# Connectors.net
KiCad netlist of a schematic drawn in Altium Designer
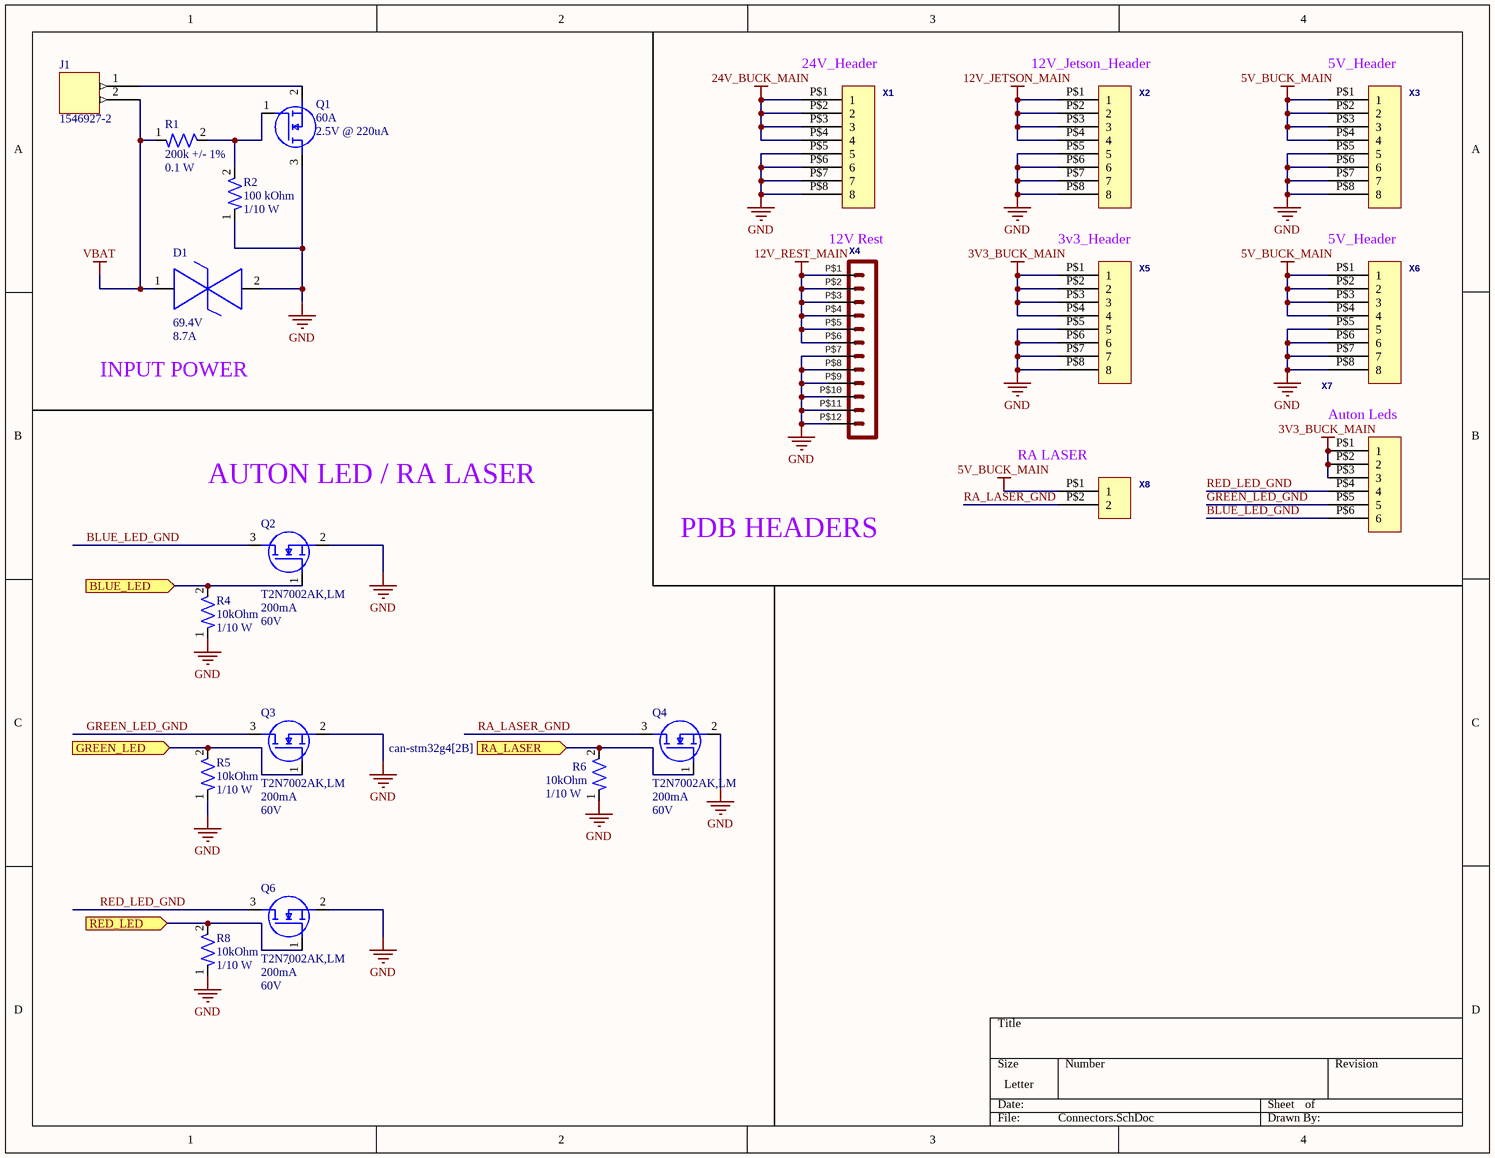
[diagram p0: Connectors.SchDoc]

(export (version "E")
  (design (tool "Eeschema 10.0.6"))
  (components
    (comp (ref "D1")
      (value "SMBJE43CAH")
      (footprint "DO-214AA (SMBJ)")
      (description "69.4V Clamp 8.7A Ipp Tvs Diode Surface Mount DO-214AA (SMBJ)")
      (fields (field (name "VCLAMP") "69.4V") (field (name "PEAK PULSER CURRENT") "8.7A"))
      (libsource (lib "MasterLib") (part "DIO-69.4V-0001"))
    )
    (comp (ref "J1")
      (value "1546927-2")
      (footprint "CONN-1546927-2")
      (libsource (lib "MasterLib") (part "CON-2POS-0003"))
    )
    (comp (ref "Q1")
      (value "TPH7R006PL,L1Q")
      (footprint "NMOS-8PowerVDFN")
      (description "N-Channel 60 V 60A (Tc) 81W (Tc) Surface Mount 8-SOP Advance (5x5)")
      (fields (field (name "DRAIN CURRENT") "60A") (field (name "VGS") "2.5V @ 220uA"))
      (libsource (lib "MasterLib") (part "NMOS-60A-0001"))
    )
    (comp (ref "Q2")
      (value "T2N7002AK,LM")
      (footprint "NMOS-SOT23-3")
      (description "MOSFET N-CH 60V 200MA SOT23")
      (fields
        (field (name "MANUFACTURER") "Toshiba")
        (field (name "ID-CONTINUOUS") "200mA")
        (field (name "VDS-MAX") "60V")
      )
      (libsource (lib "MasterLib") (part "NMOS-200MA-0001"))
    )
    (comp (ref "Q3")
      (value "T2N7002AK,LM")
      (footprint "NMOS-SOT23-3")
      (description "MOSFET N-CH 60V 200MA SOT23")
      (fields
        (field (name "MANUFACTURER") "Toshiba")
        (field (name "ID-CONTINUOUS") "200mA")
        (field (name "VDS-MAX") "60V")
      )
      (libsource (lib "MasterLib") (part "NMOS-200MA-0001"))
    )
    (comp (ref "Q4")
      (value "T2N7002AK,LM")
      (footprint "NMOS-SOT23-3")
      (description "MOSFET N-CH 60V 200MA SOT23")
      (fields
        (field (name "MANUFACTURER") "Toshiba")
        (field (name "ID-CONTINUOUS") "200mA")
        (field (name "VDS-MAX") "60V")
      )
      (libsource (lib "MasterLib") (part "NMOS-200MA-0001"))
    )
    (comp (ref "Q6")
      (value "T2N7002AK,LM")
      (footprint "NMOS-SOT23-3")
      (description "MOSFET N-CH 60V 200MA SOT23")
      (fields
        (field (name "MANUFACTURER") "Toshiba")
        (field (name "ID-CONTINUOUS") "200mA")
        (field (name "VDS-MAX") "60V")
      )
      (libsource (lib "MasterLib") (part "NMOS-200MA-0001"))
    )
    (comp (ref "R1")
      (value "ERJ-3EKF2003V")
      (footprint "RES-0603")
      (description "200 kOhms ±1% 0.1W, 1/10W Chip Resistor 0603 (1608 Metric) Automotive AEC-Q200 Thick Film")
      (fields
        (field (name "MANUFACTURER") "Panasonic Electronic Components")
        (field (name "RESISTANCE") "200k +/- 1%")
        (field (name "POWER RATING") "0.1 W")
      )
      (libsource (lib "MasterLib") (part "RES-200K-0001"))
    )
    (comp (ref "R2")
      (value "RC0603FR-07100KL")
      (footprint "RES-0603")
      (description "100 kOhms ±1% 0.1W, 1/10W Chip Resistor 0603 (1608 Metric) Moisture Resistant Thick Film")
      (fields
        (field (name "TOLERANCE") "+/- 1%")
        (field (name "RESISTANCE") "100 kOhm")
        (field (name "POWER") "1/10 W")
      )
      (libsource (lib "MasterLib") (part "RES-100K-0003"))
    )
    (comp (ref "R4")
      (value "RMCF0603ZT0R00")
      (footprint "RES-0603")
      (description "0 Ohms Jumper 0.1W, 1/10W Chip Resistor 0603 (1608 Metric) Automotive AEC-Q200 Thick Film")
      (fields (field (name "RESISTANCE") "10kOhm") (field (name "POWER") "1/10 W"))
      (libsource (lib "MasterLib") (part "RES-0-0001"))
    )
    (comp (ref "R5")
      (value "RMCF0603ZT0R00")
      (footprint "RES-0603")
      (description "0 Ohms Jumper 0.1W, 1/10W Chip Resistor 0603 (1608 Metric) Automotive AEC-Q200 Thick Film")
      (fields (field (name "RESISTANCE") "10kOhm") (field (name "POWER") "1/10 W"))
      (libsource (lib "MasterLib") (part "RES-0-0001"))
    )
    (comp (ref "R6")
      (value "RMCF0603ZT0R00")
      (footprint "RES-0603")
      (description "0 Ohms Jumper 0.1W, 1/10W Chip Resistor 0603 (1608 Metric) Automotive AEC-Q200 Thick Film")
      (fields (field (name "RESISTANCE") "10kOhm") (field (name "POWER") "1/10 W"))
      (libsource (lib "MasterLib") (part "RES-0-0001"))
    )
    (comp (ref "R8")
      (value "RMCF0603ZT0R00")
      (footprint "RES-0603")
      (description "0 Ohms Jumper 0.1W, 1/10W Chip Resistor 0603 (1608 Metric) Automotive AEC-Q200 Thick Film")
      (fields (field (name "RESISTANCE") "10kOhm") (field (name "POWER") "1/10 W"))
      (libsource (lib "MasterLib") (part "RES-0-0001"))
    )
    (comp (ref "X1")
      (value "Molex 43045-0812")
      (footprint "43045-0812")
      (libsource (lib "Molex Microfit") (part "Micro-Fit Molex 8 Pin 2 Row Vertical"))
    )
    (comp (ref "X2")
      (value "Molex 43045-0812")
      (footprint "43045-0812")
      (libsource (lib "Molex Microfit") (part "Micro-Fit Molex 8 Pin 2 Row Vertical"))
    )
    (comp (ref "X3")
      (value "Molex 43045-0812")
      (footprint "43045-0812")
      (libsource (lib "Molex Microfit") (part "Micro-Fit Molex 8 Pin 2 Row Vertical"))
    )
    (comp (ref "X4")
      (value "Molex - Micro-Fit 3.0 Series connector,  3.00mm (0.118\") pitch header, 12 positions.")
      (footprint "43045-1212")
      (libsource (lib "Molex Microfit") (part "HEADER_POS12_?43045-1212"))
    )
    (comp (ref "X5")
      (value "Molex 43045-0812")
      (footprint "43045-0812")
      (libsource (lib "Molex Microfit") (part "Micro-Fit Molex 8 Pin 2 Row Vertical"))
    )
    (comp (ref "X6")
      (value "Molex 43045-0812")
      (footprint "43045-0812")
      (libsource (lib "Molex Microfit") (part "Micro-Fit Molex 8 Pin 2 Row Vertical"))
    )
    (comp (ref "X7")
      (value "Molex 43045-0612")
      (footprint "43045-0612")
      (libsource (lib "Molex Microfit") (part "Micro-Fit Molex 6 Pin 2 Row Vertical"))
    )
    (comp (ref "X8")
      (value "Molex 43650-0215")
      (footprint "43650-0215")
      (libsource (lib "Molex Microfit") (part "Micro-Fit Molex 2 Pin Vertical"))
    )
  )
  (nets
    (net (code "1") (name "/BLUE_LED") (class "Default")
      (node (ref "Q2") (pin "1") (pinfunction "G_1") (pintype "passive"))
      (node (ref "R4") (pin "2") (pinfunction "2_2") (pintype "passive"))
    )
    (net (code "2") (name "/BLUE_LED_GND") (class "Default")
      (node (ref "Q2") (pin "3") (pinfunction "D_3") (pintype "passive"))
      (node (ref "X7") (pin "P$6") (pinfunction "6_P$6") (pintype "passive"))
    )
    (net (code "3") (name "/GREEN_LED") (class "Default")
      (node (ref "Q3") (pin "1") (pinfunction "G_1") (pintype "passive"))
      (node (ref "R5") (pin "2") (pinfunction "2_2") (pintype "passive"))
    )
    (net (code "4") (name "/GREEN_LED_GND") (class "Default")
      (node (ref "Q3") (pin "3") (pinfunction "D_3") (pintype "passive"))
      (node (ref "X7") (pin "P$5") (pinfunction "5_P$5") (pintype "passive"))
    )
    (net (code "5") (name "/RA_LASER") (class "Default")
      (node (ref "Q4") (pin "1") (pinfunction "G_1") (pintype "passive"))
      (node (ref "R6") (pin "2") (pinfunction "2_2") (pintype "passive"))
    )
    (net (code "6") (name "/RA_LASER_GND") (class "Default")
      (node (ref "Q4") (pin "3") (pinfunction "D_3") (pintype "passive"))
      (node (ref "X8") (pin "P$2") (pinfunction "2_P$2") (pintype "passive"))
    )
    (net (code "7") (name "/RED_LED") (class "Default")
      (node (ref "Q6") (pin "1") (pinfunction "G_1") (pintype "passive"))
      (node (ref "R8") (pin "2") (pinfunction "2_2") (pintype "passive"))
    )
    (net (code "8") (name "/RED_LED_GND") (class "Default")
      (node (ref "Q6") (pin "3") (pinfunction "D_3") (pintype "passive"))
      (node (ref "X7") (pin "P$4") (pinfunction "4_P$4") (pintype "passive"))
    )
    (net (code "9") (name "3V3_BUCK_MAIN") (class "Default")
      (node (ref "X5") (pin "P$1") (pinfunction "1_P$1") (pintype "passive"))
      (node (ref "X5") (pin "P$2") (pinfunction "2_P$2") (pintype "passive"))
      (node (ref "X5") (pin "P$3") (pinfunction "3_P$3") (pintype "passive"))
      (node (ref "X5") (pin "P$4") (pinfunction "4_P$4") (pintype "passive"))
      (node (ref "X7") (pin "P$1") (pinfunction "1_P$1") (pintype "passive"))
      (node (ref "X7") (pin "P$2") (pinfunction "2_P$2") (pintype "passive"))
      (node (ref "X7") (pin "P$3") (pinfunction "3_P$3") (pintype "passive"))
    )
    (net (code "10") (name "5V_BUCK_MAIN") (class "Default")
      (node (ref "X3") (pin "P$1") (pinfunction "1_P$1") (pintype "passive"))
      (node (ref "X3") (pin "P$2") (pinfunction "2_P$2") (pintype "passive"))
      (node (ref "X3") (pin "P$3") (pinfunction "3_P$3") (pintype "passive"))
      (node (ref "X3") (pin "P$4") (pinfunction "4_P$4") (pintype "passive"))
      (node (ref "X6") (pin "P$1") (pinfunction "1_P$1") (pintype "passive"))
      (node (ref "X6") (pin "P$2") (pinfunction "2_P$2") (pintype "passive"))
      (node (ref "X6") (pin "P$3") (pinfunction "3_P$3") (pintype "passive"))
      (node (ref "X6") (pin "P$4") (pinfunction "4_P$4") (pintype "passive"))
      (node (ref "X8") (pin "P$1") (pinfunction "1_P$1") (pintype "passive"))
    )
    (net (code "11") (name "12V_JETSON_MAIN") (class "Default")
      (node (ref "X2") (pin "P$1") (pinfunction "1_P$1") (pintype "passive"))
      (node (ref "X2") (pin "P$2") (pinfunction "2_P$2") (pintype "passive"))
      (node (ref "X2") (pin "P$3") (pinfunction "3_P$3") (pintype "passive"))
      (node (ref "X2") (pin "P$4") (pinfunction "4_P$4") (pintype "passive"))
    )
    (net (code "12") (name "12V_REST_MAIN") (class "Default")
      (node (ref "X4") (pin "P$1") (pinfunction "1_P$1") (pintype "passive"))
      (node (ref "X4") (pin "P$2") (pinfunction "2_P$2") (pintype "passive"))
      (node (ref "X4") (pin "P$3") (pinfunction "3_P$3") (pintype "passive"))
      (node (ref "X4") (pin "P$4") (pinfunction "4_P$4") (pintype "passive"))
      (node (ref "X4") (pin "P$5") (pinfunction "5_P$5") (pintype "passive"))
      (node (ref "X4") (pin "P$6") (pinfunction "6_P$6") (pintype "passive"))
    )
    (net (code "13") (name "24V_BUCK_MAIN") (class "Default")
      (node (ref "X1") (pin "P$1") (pinfunction "1_P$1") (pintype "passive"))
      (node (ref "X1") (pin "P$2") (pinfunction "2_P$2") (pintype "passive"))
      (node (ref "X1") (pin "P$3") (pinfunction "3_P$3") (pintype "passive"))
      (node (ref "X1") (pin "P$4") (pinfunction "4_P$4") (pintype "passive"))
    )
    (net (code "14") (name "GND") (class "Default")
      (node (ref "D1") (pin "2") (pintype "passive"))
      (node (ref "Q1") (pin "3") (pinfunction "D_3") (pintype "passive"))
      (node (ref "Q2") (pin "2") (pinfunction "S_2") (pintype "passive"))
      (node (ref "Q3") (pin "2") (pinfunction "S_2") (pintype "passive"))
      (node (ref "Q4") (pin "2") (pinfunction "S_2") (pintype "passive"))
      (node (ref "Q6") (pin "2") (pinfunction "S_2") (pintype "passive"))
      (node (ref "R2") (pin "1") (pinfunction "1_1") (pintype "passive"))
      (node (ref "R4") (pin "1") (pinfunction "1_1") (pintype "passive"))
      (node (ref "R5") (pin "1") (pinfunction "1_1") (pintype "passive"))
      (node (ref "R6") (pin "1") (pinfunction "1_1") (pintype "passive"))
      (node (ref "R8") (pin "1") (pinfunction "1_1") (pintype "passive"))
      (node (ref "X1") (pin "P$5") (pinfunction "5_P$5") (pintype "passive"))
      (node (ref "X1") (pin "P$6") (pinfunction "6_P$6") (pintype "passive"))
      (node (ref "X1") (pin "P$7") (pinfunction "7_P$7") (pintype "passive"))
      (node (ref "X1") (pin "P$8") (pinfunction "8_P$8") (pintype "passive"))
      (node (ref "X2") (pin "P$5") (pinfunction "5_P$5") (pintype "passive"))
      (node (ref "X2") (pin "P$6") (pinfunction "6_P$6") (pintype "passive"))
      (node (ref "X2") (pin "P$7") (pinfunction "7_P$7") (pintype "passive"))
      (node (ref "X2") (pin "P$8") (pinfunction "8_P$8") (pintype "passive"))
      (node (ref "X3") (pin "P$5") (pinfunction "5_P$5") (pintype "passive"))
      (node (ref "X3") (pin "P$6") (pinfunction "6_P$6") (pintype "passive"))
      (node (ref "X3") (pin "P$7") (pinfunction "7_P$7") (pintype "passive"))
      (node (ref "X3") (pin "P$8") (pinfunction "8_P$8") (pintype "passive"))
      (node (ref "X4") (pin "P$10") (pinfunction "10_P$10") (pintype "passive"))
      (node (ref "X4") (pin "P$11") (pinfunction "11_P$11") (pintype "passive"))
      (node (ref "X4") (pin "P$12") (pinfunction "12_P$12") (pintype "passive"))
      (node (ref "X4") (pin "P$7") (pinfunction "7_P$7") (pintype "passive"))
      (node (ref "X4") (pin "P$8") (pinfunction "8_P$8") (pintype "passive"))
      (node (ref "X4") (pin "P$9") (pinfunction "9_P$9") (pintype "passive"))
      (node (ref "X5") (pin "P$5") (pinfunction "5_P$5") (pintype "passive"))
      (node (ref "X5") (pin "P$6") (pinfunction "6_P$6") (pintype "passive"))
      (node (ref "X5") (pin "P$7") (pinfunction "7_P$7") (pintype "passive"))
      (node (ref "X5") (pin "P$8") (pinfunction "8_P$8") (pintype "passive"))
      (node (ref "X6") (pin "P$5") (pinfunction "5_P$5") (pintype "passive"))
      (node (ref "X6") (pin "P$6") (pinfunction "6_P$6") (pintype "passive"))
      (node (ref "X6") (pin "P$7") (pinfunction "7_P$7") (pintype "passive"))
      (node (ref "X6") (pin "P$8") (pinfunction "8_P$8") (pintype "passive"))
    )
    (net (code "15") (name "Net-(Q1-G)") (class "Default")
      (node (ref "Q1") (pin "1") (pinfunction "G_1") (pintype "passive"))
      (node (ref "R1") (pin "2") (pinfunction "2_2") (pintype "passive"))
      (node (ref "R2") (pin "2") (pinfunction "2_2") (pintype "passive"))
    )
    (net (code "16") (name "Net-(Q1-S)") (class "Default")
      (node (ref "J1") (pin "1") (pintype "output"))
      (node (ref "Q1") (pin "2") (pinfunction "S_2") (pintype "passive"))
    )
    (net (code "17") (name "VBAT") (class "Default")
      (node (ref "D1") (pin "1") (pintype "passive"))
      (node (ref "J1") (pin "2") (pintype "output"))
      (node (ref "R1") (pin "1") (pinfunction "1_1") (pintype "passive"))
    )
  )
)
